# P11_Hi3531A_SYSTEM_RES.net
KiCad netlist of a schematic drawn in Altium Designer
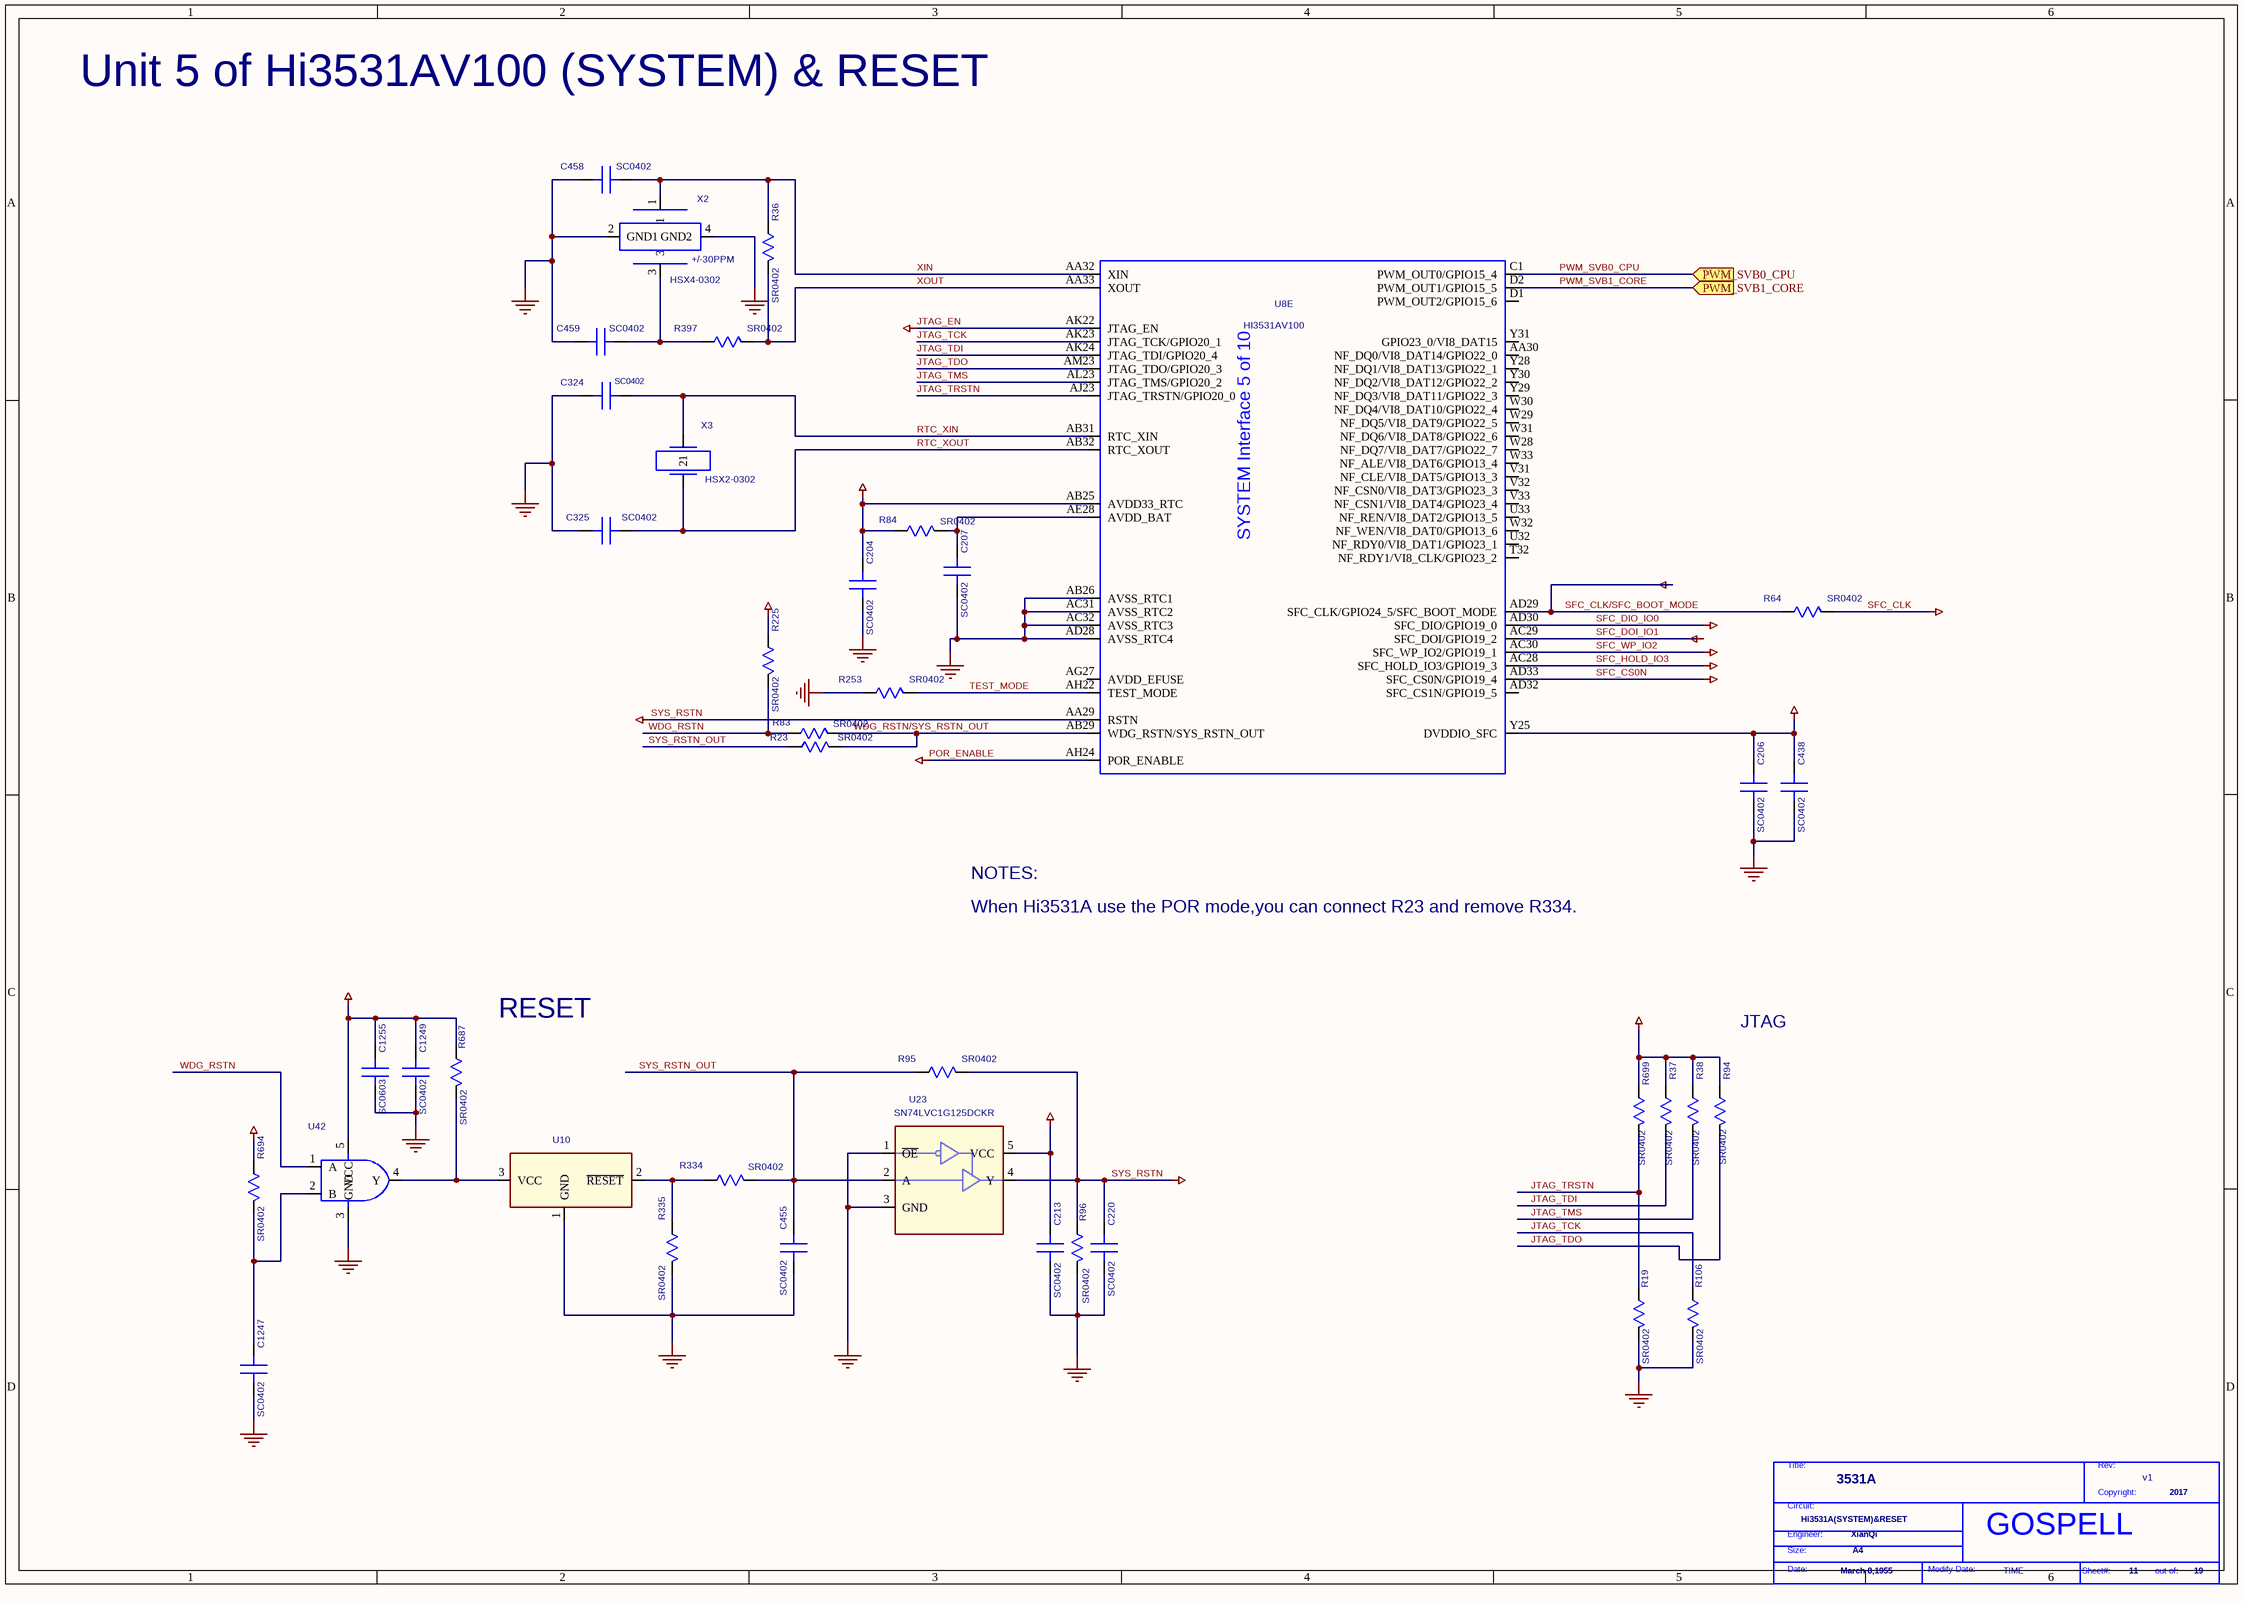
[diagram p0: P11 Hi3531A(SYSTEM)&RES.SchDoc]

(export (version "E")
  (design (tool "Eeschema 10.0.6"))
  (components
    (comp (ref "C204") (value "SC0402") (libsource (lib "*") (part "C_0_Dup2")))
    (comp (ref "C206") (value "SC0402") (libsource (lib "*") (part "C_0_Dup2")))
    (comp (ref "C207") (value "SC0402") (libsource (lib "*") (part "C_0_Dup2")))
    (comp (ref "C213") (value "SC0402") (libsource (lib "*") (part "C_0_Dup2")))
    (comp (ref "C220") (value "SC0402") (libsource (lib "*") (part "C_0_Dup2")))
    (comp (ref "C324") (value "SC0402") (libsource (lib "*") (part "C_0_Dup2")))
    (comp (ref "C325") (value "SC0402") (libsource (lib "*") (part "C_0_Dup2")))
    (comp (ref "C438") (value "SC0402") (libsource (lib "*") (part "C_0_Dup2")))
    (comp (ref "C455") (value "SC0402") (libsource (lib "*") (part "C_0_Dup2")))
    (comp (ref "C458") (value "SC0402") (libsource (lib "*") (part "C_0_Dup2")))
    (comp (ref "C459") (value "SC0402") (libsource (lib "*") (part "C_0_Dup2")))
    (comp (ref "C1247") (value "SC0402") (libsource (lib "*") (part "C_0_Dup2")))
    (comp (ref "C1249") (value "SC0402") (libsource (lib "*") (part "C_0_Dup2")))
    (comp (ref "C1255") (value "SC0603") (libsource (lib "*") (part "C_0_Dup2")))
    (comp (ref "R19") (value "SR0402") (libsource (lib "*") (part "R_2")))
    (comp (ref "R23") (value "SR0402") (libsource (lib "*") (part "R_1")))
    (comp (ref "R36") (value "SR0402") (libsource (lib "*") (part "R_1")))
    (comp (ref "R37") (value "SR0402") (libsource (lib "*") (part "R_2")))
    (comp (ref "R38") (value "SR0402") (libsource (lib "*") (part "R_2")))
    (comp (ref "R64") (value "SR0402") (libsource (lib "*") (part "R_1")))
    (comp (ref "R83") (value "SR0402") (libsource (lib "*") (part "R_1")))
    (comp (ref "R84") (value "SR0402") (libsource (lib "*") (part "R_1")))
    (comp (ref "R94") (value "SR0402") (libsource (lib "*") (part "R_2")))
    (comp (ref "R95") (value "SR0402") (libsource (lib "*") (part "R_1")))
    (comp (ref "R96") (value "SR0402") (libsource (lib "*") (part "R_1")))
    (comp (ref "R106") (value "SR0402") (libsource (lib "*") (part "R_2")))
    (comp (ref "R225") (value "SR0402") (libsource (lib "*") (part "R_1")))
    (comp (ref "R253") (value "SR0402") (libsource (lib "*") (part "R_1")))
    (comp (ref "R334") (value "SR0402") (libsource (lib "*") (part "R_1")))
    (comp (ref "R335") (value "SR0402") (libsource (lib "*") (part "R_1")))
    (comp (ref "R397") (value "SR0402") (libsource (lib "*") (part "R_1")))
    (comp (ref "R687") (value "SR0402") (libsource (lib "*") (part "R_1")))
    (comp (ref "R694") (value "SR0402") (libsource (lib "*") (part "R_1")))
    (comp (ref "R699") (value "SR0402") (libsource (lib "*") (part "R_2")))
    (comp (ref "U8")
      (value "BGA805-32-3333")
      (fields (field (name "DEVICE") "HI3531AV100"))
      (libsource (lib "*") (part "HI3531AV100_M2_17"))
    )
    (comp (ref "U10") (value "SOT23B") (libsource (lib "*") (part "ADM809_0")))
    (comp (ref "U23")
      (value "HSOT-SC70-DCK")
      (fields (field (name "DEVICE") "SN74LVC1G125DCKR"))
      (libsource (lib "*") (part "SN74LVC1G125Q-Q1_1"))
    )
    (comp (ref "U42") (value "SOT23-5C") (libsource (lib "*") (part "NC7SZ08P5X_0")))
    (comp (ref "X2") (value "HSX4-0302") (libsource (lib "*") (part "X_B_7")))
    (comp (ref "X3") (value "HSX2-0302") (libsource (lib "*") (part "X_1")))
  )
  (nets
    (net (code "1") (name "/JTAG_TCK") (class "Default")
      (node (ref "R106") (pin "1") (pinfunction "A_1") (pintype "passive"))
      (node (ref "U8") (pin "AK23") (pinfunction "JTAG_TCK/GPIO20_1_AK23") (pintype "passive"))
    )
    (net (code "2") (name "/JTAG_TDI") (class "Default")
      (node (ref "R37") (pin "2") (pinfunction "B_2") (pintype "passive"))
      (node (ref "U8") (pin "AK24") (pinfunction "JTAG_TDI/GPIO20_4_AK24") (pintype "passive"))
    )
    (net (code "3") (name "/JTAG_TDO") (class "Default")
      (node (ref "R94") (pin "2") (pinfunction "B_2") (pintype "passive"))
      (node (ref "U8") (pin "AM23") (pinfunction "JTAG_TDO/GPIO20_3_AM23") (pintype "passive"))
    )
    (net (code "4") (name "/JTAG_TMS") (class "Default")
      (node (ref "R38") (pin "2") (pinfunction "B_2") (pintype "passive"))
      (node (ref "U8") (pin "AL23") (pinfunction "JTAG_TMS/GPIO20_2_AL23") (pintype "passive"))
    )
    (net (code "5") (name "/JTAG_TRSTN") (class "Default")
      (node (ref "R19") (pin "1") (pinfunction "A_1") (pintype "passive"))
      (node (ref "R699") (pin "2") (pinfunction "B_2") (pintype "passive"))
      (node (ref "U8") (pin "AJ23") (pinfunction "JTAG_TRSTN/GPIO20_0_AJ23") (pintype "passive"))
    )
    (net (code "6") (name "/PWM_SVB0_CPU") (class "Default")
      (node (ref "U8") (pin "C1") (pinfunction "PWM_OUT0/GPIO15_4_C1") (pintype "passive"))
    )
    (net (code "7") (name "/PWM_SVB1_CORE") (class "Default")
      (node (ref "U8") (pin "D2") (pinfunction "PWM_OUT1/GPIO15_5_D2") (pintype "passive"))
    )
    (net (code "8") (name "/RTC_XIN") (class "Default")
      (node (ref "C324") (pin "2") (pinfunction "B_2") (pintype "passive"))
      (node (ref "U8") (pin "AB31") (pinfunction "RTC_XIN_AB31") (pintype "passive"))
      (node (ref "X3") (pin "1") (pinfunction "1_1") (pintype "passive"))
    )
    (net (code "9") (name "/RTC_XOUT") (class "Default")
      (node (ref "C325") (pin "2") (pinfunction "B_2") (pintype "passive"))
      (node (ref "U8") (pin "AB32") (pinfunction "RTC_XOUT_AB32") (pintype "passive"))
      (node (ref "X3") (pin "2") (pinfunction "2_2") (pintype "passive"))
    )
    (net (code "10") (name "/SYS_RSTN_OUT") (class "Default")
      (node (ref "C455") (pin "1") (pinfunction "A_1") (pintype "passive"))
      (node (ref "R23") (pin "1") (pinfunction "A_1") (pintype "passive"))
      (node (ref "R334") (pin "2") (pinfunction "B_2") (pintype "passive"))
      (node (ref "R95") (pin "1") (pinfunction "A_1") (pintype "passive"))
      (node (ref "U23") (pin "2") (pinfunction "A_2") (pintype "passive"))
    )
    (net (code "11") (name "/TEST_MODE") (class "Default")
      (node (ref "R253") (pin "2") (pinfunction "B_2") (pintype "passive"))
      (node (ref "U8") (pin "AH22") (pinfunction "TEST_MODE_AH22") (pintype "passive"))
    )
    (net (code "12") (name "/WDG_RSTN") (class "Default")
      (node (ref "R225") (pin "2") (pinfunction "B_2") (pintype "passive"))
      (node (ref "R83") (pin "1") (pinfunction "A_1") (pintype "passive"))
      (node (ref "U42") (pin "1") (pinfunction "A_1") (pintype "passive"))
    )
    (net (code "13") (name "/WDG_RSTN{slash}SYS_RSTN_OUT") (class "Default")
      (node (ref "R23") (pin "2") (pinfunction "B_2") (pintype "passive"))
      (node (ref "R83") (pin "2") (pinfunction "B_2") (pintype "passive"))
      (node (ref "U8") (pin "AB29") (pinfunction "WDG_RSTN/SYS_RSTN_OUT_AB29") (pintype "passive"))
    )
    (net (code "14") (name "/XIN") (class "Default")
      (node (ref "C458") (pin "2") (pinfunction "B_2") (pintype "passive"))
      (node (ref "R36") (pin "1") (pinfunction "A_1") (pintype "passive"))
      (node (ref "U8") (pin "AA32") (pinfunction "XIN_AA32") (pintype "passive"))
      (node (ref "X2") (pin "1") (pinfunction "1_1") (pintype "passive"))
    )
    (net (code "15") (name "/XOUT") (class "Default")
      (node (ref "R36") (pin "2") (pinfunction "B_2") (pintype "passive"))
      (node (ref "R397") (pin "2") (pinfunction "B_2") (pintype "passive"))
      (node (ref "U8") (pin "AA33") (pinfunction "XOUT_AA33") (pintype "passive"))
    )
    (net (code "16") (name "3V3") (class "Default")
      (node (ref "C1249") (pin "1") (pinfunction "A_1") (pintype "passive"))
      (node (ref "C1255") (pin "1") (pinfunction "A_1") (pintype "passive"))
      (node (ref "C204") (pin "1") (pinfunction "A_1") (pintype "passive"))
      (node (ref "C206") (pin "1") (pinfunction "A_1") (pintype "passive"))
      (node (ref "C213") (pin "1") (pinfunction "A_1") (pintype "passive"))
      (node (ref "C438") (pin "1") (pinfunction "A_1") (pintype "passive"))
      (node (ref "R225") (pin "1") (pinfunction "A_1") (pintype "passive"))
      (node (ref "R37") (pin "1") (pinfunction "A_1") (pintype "passive"))
      (node (ref "R38") (pin "1") (pinfunction "A_1") (pintype "passive"))
      (node (ref "R687") (pin "1") (pinfunction "A_1") (pintype "passive"))
      (node (ref "R694") (pin "1") (pinfunction "A_1") (pintype "passive"))
      (node (ref "R699") (pin "1") (pinfunction "A_1") (pintype "passive"))
      (node (ref "R84") (pin "1") (pinfunction "A_1") (pintype "passive"))
      (node (ref "R94") (pin "1") (pinfunction "A_1") (pintype "passive"))
      (node (ref "U23") (pin "5") (pinfunction "VCC_5") (pintype "passive"))
      (node (ref "U42") (pin "5") (pinfunction "VCC_5") (pintype "passive"))
      (node (ref "U8") (pin "AB25") (pinfunction "AVDD33_RTC_AB25") (pintype "passive"))
      (node (ref "U8") (pin "Y25") (pinfunction "DVDDIO_SFC_Y25") (pintype "passive"))
    )
    (net (code "17") (name "GND") (class "Default")
      (node (ref "C1247") (pin "2") (pinfunction "B_2") (pintype "passive"))
      (node (ref "C1249") (pin "2") (pinfunction "B_2") (pintype "passive"))
      (node (ref "C1255") (pin "2") (pinfunction "B_2") (pintype "passive"))
      (node (ref "C204") (pin "2") (pinfunction "B_2") (pintype "passive"))
      (node (ref "C206") (pin "2") (pinfunction "B_2") (pintype "passive"))
      (node (ref "C207") (pin "2") (pinfunction "B_2") (pintype "passive"))
      (node (ref "C213") (pin "2") (pinfunction "B_2") (pintype "passive"))
      (node (ref "C220") (pin "2") (pinfunction "B_2") (pintype "passive"))
      (node (ref "C324") (pin "1") (pinfunction "A_1") (pintype "passive"))
      (node (ref "C325") (pin "1") (pinfunction "A_1") (pintype "passive"))
      (node (ref "C438") (pin "2") (pinfunction "B_2") (pintype "passive"))
      (node (ref "C455") (pin "2") (pinfunction "B_2") (pintype "passive"))
      (node (ref "C458") (pin "1") (pinfunction "A_1") (pintype "passive"))
      (node (ref "C459") (pin "1") (pinfunction "A_1") (pintype "passive"))
      (node (ref "R106") (pin "2") (pinfunction "B_2") (pintype "passive"))
      (node (ref "R19") (pin "2") (pinfunction "B_2") (pintype "passive"))
      (node (ref "R253") (pin "1") (pinfunction "A_1") (pintype "passive"))
      (node (ref "R335") (pin "2") (pinfunction "B_2") (pintype "passive"))
      (node (ref "R96") (pin "2") (pinfunction "B_2") (pintype "passive"))
      (node (ref "U10") (pin "1") (pinfunction "GND_1") (pintype "passive"))
      (node (ref "U23") (pin "1") (pinfunction "~{OE}_1") (pintype "passive"))
      (node (ref "U23") (pin "3") (pinfunction "GND_3") (pintype "passive"))
      (node (ref "U42") (pin "3") (pinfunction "GND_3") (pintype "passive"))
      (node (ref "U8") (pin "AB26") (pinfunction "AVSS_RTC1_AB26") (pintype "passive"))
      (node (ref "U8") (pin "AC31") (pinfunction "AVSS_RTC2_AC31") (pintype "passive"))
      (node (ref "U8") (pin "AC32") (pinfunction "AVSS_RTC3_AC32") (pintype "passive"))
      (node (ref "U8") (pin "AD28") (pinfunction "AVSS_RTC4_AD28") (pintype "passive"))
      (node (ref "X2") (pin "2") (pinfunction "GND1_2") (pintype "passive"))
      (node (ref "X2") (pin "4") (pinfunction "GND2_4") (pintype "passive"))
    )
    (net (code "18") (name "JTAG_EN") (class "Default")
      (node (ref "U8") (pin "AK22") (pinfunction "JTAG_EN_AK22") (pintype "passive"))
    )
    (net (code "19") (name "Net-(C207-A)") (class "Default")
      (node (ref "C207") (pin "1") (pinfunction "A_1") (pintype "passive"))
      (node (ref "R84") (pin "2") (pinfunction "B_2") (pintype "passive"))
      (node (ref "U8") (pin "AE28") (pinfunction "AVDD_BAT_AE28") (pintype "passive"))
    )
    (net (code "20") (name "Net-(C459-B)") (class "Default")
      (node (ref "C459") (pin "2") (pinfunction "B_2") (pintype "passive"))
      (node (ref "R397") (pin "1") (pinfunction "A_1") (pintype "passive"))
      (node (ref "X2") (pin "3") (pinfunction "3_3") (pintype "passive"))
    )
    (net (code "21") (name "Net-(C1247-A)") (class "Default")
      (node (ref "C1247") (pin "1") (pinfunction "A_1") (pintype "passive"))
      (node (ref "R694") (pin "2") (pinfunction "B_2") (pintype "passive"))
      (node (ref "U42") (pin "2") (pinfunction "B_2") (pintype "passive"))
    )
    (net (code "22") (name "Net-(R334-A)") (class "Default")
      (node (ref "R334") (pin "1") (pinfunction "A_1") (pintype "passive"))
      (node (ref "R335") (pin "1") (pinfunction "A_1") (pintype "passive"))
      (node (ref "U10") (pin "2") (pinfunction "~{RESET}_2") (pintype "passive"))
    )
    (net (code "23") (name "Net-(R687-B)") (class "Default")
      (node (ref "R687") (pin "2") (pinfunction "B_2") (pintype "passive"))
      (node (ref "U10") (pin "3") (pinfunction "VCC_3") (pintype "passive"))
      (node (ref "U42") (pin "4") (pinfunction "Y_4") (pintype "passive"))
    )
    (net (code "24") (name "POR_ENABLE") (class "Default")
      (node (ref "U8") (pin "AH24") (pinfunction "POR_ENABLE_AH24") (pintype "passive"))
    )
    (net (code "25") (name "SFC_CLK") (class "Default")
      (node (ref "R64") (pin "2") (pinfunction "B_2") (pintype "passive"))
    )
    (net (code "26") (name "SFC_CLK{slash}SFC_BOOT_MODE") (class "Default")
      (node (ref "R64") (pin "1") (pinfunction "A_1") (pintype "passive"))
      (node (ref "U8") (pin "AD29") (pinfunction "SFC_CLK/GPIO24_5/SFC_BOOT_MODE_AD29") (pintype "passive"))
    )
    (net (code "27") (name "SFC_CS0N") (class "Default")
      (node (ref "U8") (pin "AD33") (pinfunction "SFC_CS0N/GPIO19_4_AD33") (pintype "passive"))
    )
    (net (code "28") (name "SFC_DIO_IO0") (class "Default")
      (node (ref "U8") (pin "AD30") (pinfunction "SFC_DIO/GPIO19_0_AD30") (pintype "passive"))
    )
    (net (code "29") (name "SFC_DOI_IO1") (class "Default")
      (node (ref "U8") (pin "AC29") (pinfunction "SFC_DOI/GPIO19_2_AC29") (pintype "passive"))
    )
    (net (code "30") (name "SFC_HOLD_IO3") (class "Default")
      (node (ref "U8") (pin "AC28") (pinfunction "SFC_HOLD_IO3/GPIO19_3_AC28") (pintype "passive"))
    )
    (net (code "31") (name "SFC_WP_IO2") (class "Default")
      (node (ref "U8") (pin "AC30") (pinfunction "SFC_WP_IO2/GPIO19_1_AC30") (pintype "passive"))
    )
    (net (code "32") (name "SYS_RSTN") (class "Default")
      (node (ref "C220") (pin "1") (pinfunction "A_1") (pintype "passive"))
      (node (ref "R95") (pin "2") (pinfunction "B_2") (pintype "passive"))
      (node (ref "R96") (pin "1") (pinfunction "A_1") (pintype "passive"))
      (node (ref "U23") (pin "4") (pinfunction "Y_4") (pintype "passive"))
      (node (ref "U8") (pin "AA29") (pinfunction "RSTN_AA29") (pintype "passive"))
    )
    (net (code "33") (name "unconnected-(U8E-AVDD_EFUSE-PadAG27)") (class "Default")
      (node (ref "U8") (pin "AG27") (pinfunction "AVDD_EFUSE_AG27") (pintype "passive"))
    )
    (net (code "34") (name "unconnected-(U8E-GPIO23_0{slash}VI8_DAT15-PadY31)") (class "Default")
      (node (ref "U8") (pin "Y31") (pinfunction "GPIO23_0/VI8_DAT15_Y31") (pintype "passive"))
    )
    (net (code "35") (name "unconnected-(U8E-NF_ALE{slash}VI8_DAT6{slash}GPIO13_4-PadW33)") (class "Default")
      (node (ref "U8") (pin "W33") (pinfunction "NF_ALE/VI8_DAT6/GPIO13_4_W33") (pintype "passive"))
    )
    (net (code "36") (name "unconnected-(U8E-NF_CLE{slash}VI8_DAT5{slash}GPIO13_3-PadV31)") (class "Default")
      (node (ref "U8") (pin "V31") (pinfunction "NF_CLE/VI8_DAT5/GPIO13_3_V31") (pintype "passive"))
    )
    (net (code "37") (name "unconnected-(U8E-NF_CSN0{slash}VI8_DAT3{slash}GPIO23_3-PadV32)") (class "Default")
      (node (ref "U8") (pin "V32") (pinfunction "NF_CSN0/VI8_DAT3/GPIO23_3_V32") (pintype "passive"))
    )
    (net (code "38") (name "unconnected-(U8E-NF_CSN1{slash}VI8_DAT4{slash}GPIO23_4-PadV33)") (class "Default")
      (node (ref "U8") (pin "V33") (pinfunction "NF_CSN1/VI8_DAT4/GPIO23_4_V33") (pintype "passive"))
    )
    (net (code "39") (name "unconnected-(U8E-NF_DQ0{slash}VI8_DAT14{slash}GPIO22_0-PadAA30)") (class "Default")
      (node (ref "U8") (pin "AA30") (pinfunction "NF_DQ0/VI8_DAT14/GPIO22_0_AA30") (pintype "passive"))
    )
    (net (code "40") (name "unconnected-(U8E-NF_DQ1{slash}VI8_DAT13{slash}GPIO22_1-PadY28)") (class "Default")
      (node (ref "U8") (pin "Y28") (pinfunction "NF_DQ1/VI8_DAT13/GPIO22_1_Y28") (pintype "passive"))
    )
    (net (code "41") (name "unconnected-(U8E-NF_DQ2{slash}VI8_DAT12{slash}GPIO22_2-PadY30)") (class "Default")
      (node (ref "U8") (pin "Y30") (pinfunction "NF_DQ2/VI8_DAT12/GPIO22_2_Y30") (pintype "passive"))
    )
    (net (code "42") (name "unconnected-(U8E-NF_DQ3{slash}VI8_DAT11{slash}GPIO22_3-PadY29)") (class "Default")
      (node (ref "U8") (pin "Y29") (pinfunction "NF_DQ3/VI8_DAT11/GPIO22_3_Y29") (pintype "passive"))
    )
    (net (code "43") (name "unconnected-(U8E-NF_DQ4{slash}VI8_DAT10{slash}GPIO22_4-PadW30)") (class "Default")
      (node (ref "U8") (pin "W30") (pinfunction "NF_DQ4/VI8_DAT10/GPIO22_4_W30") (pintype "passive"))
    )
    (net (code "44") (name "unconnected-(U8E-NF_DQ5{slash}VI8_DAT9{slash}GPIO22_5-PadW29)") (class "Default")
      (node (ref "U8") (pin "W29") (pinfunction "NF_DQ5/VI8_DAT9/GPIO22_5_W29") (pintype "passive"))
    )
    (net (code "45") (name "unconnected-(U8E-NF_DQ6{slash}VI8_DAT8{slash}GPIO22_6-PadW31)") (class "Default")
      (node (ref "U8") (pin "W31") (pinfunction "NF_DQ6/VI8_DAT8/GPIO22_6_W31") (pintype "passive"))
    )
    (net (code "46") (name "unconnected-(U8E-NF_DQ7{slash}VI8_DAT7{slash}GPIO22_7-PadW28)") (class "Default")
      (node (ref "U8") (pin "W28") (pinfunction "NF_DQ7/VI8_DAT7/GPIO22_7_W28") (pintype "passive"))
    )
    (net (code "47") (name "unconnected-(U8E-NF_RDY0{slash}VI8_DAT1{slash}GPIO23_1-PadU32)") (class "Default")
      (node (ref "U8") (pin "U32") (pinfunction "NF_RDY0/VI8_DAT1/GPIO23_1_U32") (pintype "passive"))
    )
    (net (code "48") (name "unconnected-(U8E-NF_RDY1{slash}VI8_CLK{slash}GPIO23_2-PadT32)") (class "Default")
      (node (ref "U8") (pin "T32") (pinfunction "NF_RDY1/VI8_CLK/GPIO23_2_T32") (pintype "passive"))
    )
    (net (code "49") (name "unconnected-(U8E-NF_REN{slash}VI8_DAT2{slash}GPIO13_5-PadU33)") (class "Default")
      (node (ref "U8") (pin "U33") (pinfunction "NF_REN/VI8_DAT2/GPIO13_5_U33") (pintype "passive"))
    )
    (net (code "50") (name "unconnected-(U8E-NF_WEN{slash}VI8_DAT0{slash}GPIO13_6-PadW32)") (class "Default")
      (node (ref "U8") (pin "W32") (pinfunction "NF_WEN/VI8_DAT0/GPIO13_6_W32") (pintype "passive"))
    )
    (net (code "51") (name "unconnected-(U8E-PWM_OUT2{slash}GPIO15_6-PadD1)") (class "Default")
      (node (ref "U8") (pin "D1") (pinfunction "PWM_OUT2/GPIO15_6_D1") (pintype "passive"))
    )
    (net (code "52") (name "unconnected-(U8E-SFC_CS1N{slash}GPIO19_5-PadAD32)") (class "Default")
      (node (ref "U8") (pin "AD32") (pinfunction "SFC_CS1N/GPIO19_5_AD32") (pintype "passive"))
    )
  )
)
